# ports.net
KiCad netlist of a schematic drawn in Altium Designer
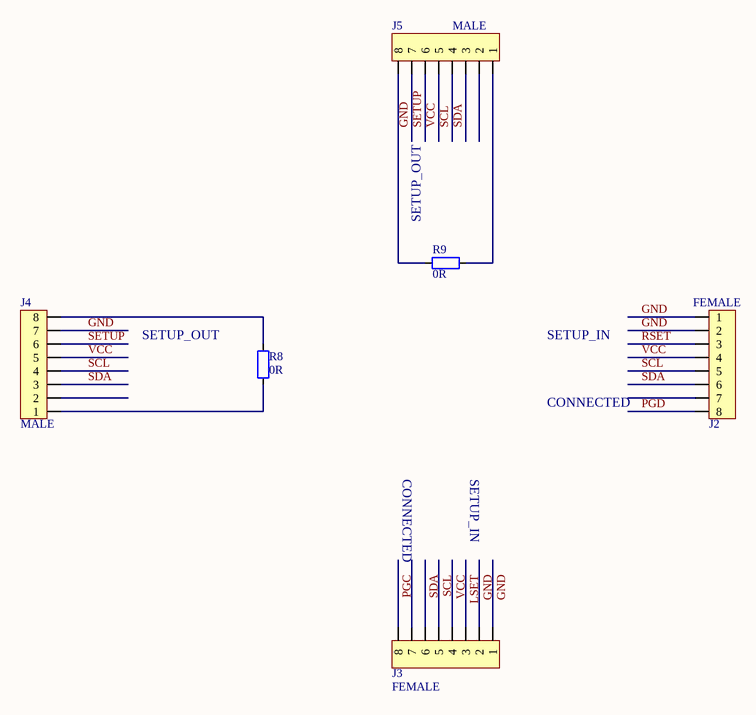
[diagram p0: ports.SchDoc]

(export (version "E")
  (design (tool "Eeschema 10.0.6"))
  (components
    (comp (ref "J2")
      (value "FEMALE")
      (footprint "PCB_ConnectorHDR:HDR1X10_2.54_180H")
      (description "Header")
      (libsource (lib "") (part "HDR1x8_2.54T_1"))
    )
    (comp (ref "J3")
      (value "FEMALE")
      (footprint "PCB_ConnectorHDR:HDR1X10_2.54_180H")
      (description "Header")
      (libsource (lib "SCH_ConnectorHDR") (part "HDR1x8_2.54T"))
    )
    (comp (ref "J4")
      (value "MALE")
      (footprint "PCB_ConnectorHDR:HDR1X10_2.54_180H")
      (description "Header")
      (libsource (lib "") (part "HDR1x8_2.54T_2"))
    )
    (comp (ref "J5")
      (value "MALE")
      (footprint "PCB_ConnectorHDR:HDR1X10_2.54_180H")
      (description "Header")
      (libsource (lib "") (part "HDR1x8_2.54T_1"))
    )
    (comp (ref "R8")
      (value "0R")
      (footprint "PCB_PassiveRes:RES_0603")
      (description "Resistor")
      (fields (field (name "Comment") "Res_0603"))
      (libsource (lib "") (part "Res_0603_1"))
    )
    (comp (ref "R9")
      (value "0R")
      (footprint "PCB_PassiveRes:RES_0603")
      (description "Resistor")
      (fields (field (name "Comment") "Res_0603"))
      (libsource (lib "SCH_Passive") (part "Res_0603"))
    )
  )
  (nets
    (net (code "1") (name "/GND") (class "Default")
      (node (ref "J2") (pin "1") (pinfunction "1_1") (pintype "passive"))
      (node (ref "J2") (pin "2") (pinfunction "2_2") (pintype "passive"))
      (node (ref "J3") (pin "1") (pinfunction "1_1") (pintype "passive"))
      (node (ref "J3") (pin "2") (pinfunction "2_2") (pintype "passive"))
      (node (ref "J4") (pin "7") (pinfunction "7_7") (pintype "passive"))
      (node (ref "J5") (pin "7") (pinfunction "7_7") (pintype "passive"))
    )
    (net (code "2") (name "/LSET") (class "Default")
      (node (ref "J3") (pin "3") (pinfunction "3_3") (pintype "passive"))
    )
    (net (code "3") (name "/PGC") (class "Default")
      (node (ref "J3") (pin "8") (pinfunction "8_8") (pintype "passive"))
    )
    (net (code "4") (name "/PGD") (class "Default")
      (node (ref "J2") (pin "8") (pinfunction "8_8") (pintype "passive"))
    )
    (net (code "5") (name "/RSET") (class "Default")
      (node (ref "J2") (pin "3") (pinfunction "3_3") (pintype "passive"))
    )
    (net (code "6") (name "/SCL") (class "Default")
      (node (ref "J2") (pin "5") (pinfunction "5_5") (pintype "passive"))
      (node (ref "J3") (pin "5") (pinfunction "5_5") (pintype "passive"))
      (node (ref "J4") (pin "4") (pinfunction "4_4") (pintype "passive"))
      (node (ref "J5") (pin "4") (pinfunction "4_4") (pintype "passive"))
    )
    (net (code "7") (name "/SDA") (class "Default")
      (node (ref "J2") (pin "6") (pinfunction "6_6") (pintype "passive"))
      (node (ref "J3") (pin "6") (pinfunction "6_6") (pintype "passive"))
      (node (ref "J4") (pin "3") (pinfunction "3_3") (pintype "passive"))
      (node (ref "J5") (pin "3") (pinfunction "3_3") (pintype "passive"))
    )
    (net (code "8") (name "/SETUP") (class "Default")
      (node (ref "J4") (pin "6") (pinfunction "6_6") (pintype "passive"))
      (node (ref "J5") (pin "6") (pinfunction "6_6") (pintype "passive"))
    )
    (net (code "9") (name "/VCC") (class "Default")
      (node (ref "J2") (pin "4") (pinfunction "4_4") (pintype "passive"))
      (node (ref "J3") (pin "4") (pinfunction "4_4") (pintype "passive"))
      (node (ref "J4") (pin "5") (pinfunction "5_5") (pintype "passive"))
      (node (ref "J5") (pin "5") (pinfunction "5_5") (pintype "passive"))
    )
    (net (code "10") (name "Net-(J4-Pad1)") (class "Default")
      (node (ref "J4") (pin "1") (pinfunction "1_1") (pintype "passive"))
      (node (ref "R8") (pin "1") (pinfunction "1_1") (pintype "passive"))
    )
    (net (code "11") (name "Net-(J4-Pad8)") (class "Default")
      (node (ref "J4") (pin "8") (pinfunction "8_8") (pintype "passive"))
      (node (ref "R8") (pin "2") (pinfunction "2_2") (pintype "passive"))
    )
    (net (code "12") (name "Net-(J5-Pad1)") (class "Default")
      (node (ref "J5") (pin "1") (pinfunction "1_1") (pintype "passive"))
      (node (ref "R9") (pin "2") (pinfunction "2_2") (pintype "passive"))
    )
    (net (code "13") (name "Net-(J5-Pad8)") (class "Default")
      (node (ref "J5") (pin "8") (pinfunction "8_8") (pintype "passive"))
      (node (ref "R9") (pin "1") (pinfunction "1_1") (pintype "passive"))
    )
    (net (code "14") (name "unconnected-(J2-Pad7)") (class "Default")
      (node (ref "J2") (pin "7") (pinfunction "7_7") (pintype "passive"))
    )
    (net (code "15") (name "unconnected-(J3-Pad7)") (class "Default")
      (node (ref "J3") (pin "7") (pinfunction "7_7") (pintype "passive"))
    )
    (net (code "16") (name "unconnected-(J4-Pad2)") (class "Default")
      (node (ref "J4") (pin "2") (pinfunction "2_2") (pintype "passive"))
    )
    (net (code "17") (name "unconnected-(J5-Pad2)") (class "Default")
      (node (ref "J5") (pin "2") (pinfunction "2_2") (pintype "passive"))
    )
  )
)
